# DriverControlsMezzanine.net
KiCad netlist of a schematic drawn in Altium Designer
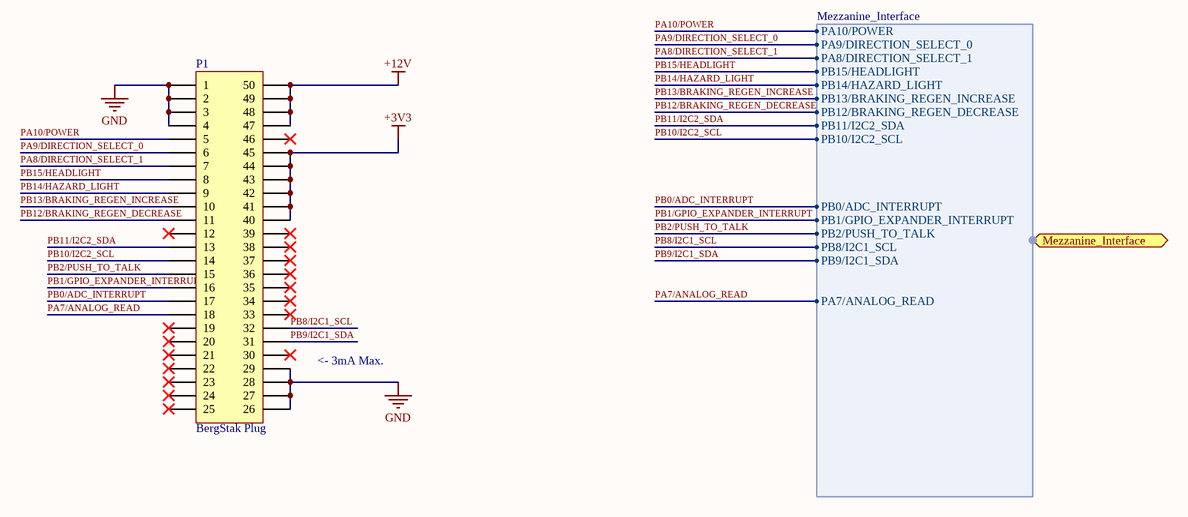
[diagram p0: DriverControlsMezzanine.SchDoc]

(export (version "E")
  (design (tool "Eeschema 10.0.6"))
  (components
    (comp (ref "P1")
      (value "CONN 50POS Bergstak Plug 0.02\"")
      (footprint "CONN, Bergstak 50 Pos Plug")
      (description "50 Position Connector Plug, Outer Shroud Contacts Surface Mount Gold")
      (fields (field (name "SERIES") "BergStak Plug"))
      (libsource (lib "Schematic Diagrams") (part "CONN 50POS Bergstak Plug 0.02{dblquote}"))
    )
  )
  (nets
    (net (code "2") (name "+3V3") (class "Default")
      (node (ref "P1") (pin "40") (pinfunction "40_40") (pintype "passive"))
      (node (ref "P1") (pin "41") (pinfunction "41_41") (pintype "passive"))
      (node (ref "P1") (pin "42") (pinfunction "42_42") (pintype "passive"))
      (node (ref "P1") (pin "43") (pinfunction "43_43") (pintype "passive"))
      (node (ref "P1") (pin "44") (pinfunction "44_44") (pintype "passive"))
      (node (ref "P1") (pin "45") (pinfunction "45_45") (pintype "passive"))
    )
    (net (code "3") (name "+12V") (class "Default")
      (node (ref "P1") (pin "47") (pinfunction "47_47") (pintype "passive"))
      (node (ref "P1") (pin "48") (pinfunction "48_48") (pintype "passive"))
      (node (ref "P1") (pin "49") (pinfunction "49_49") (pintype "passive"))
      (node (ref "P1") (pin "50") (pinfunction "50_50") (pintype "passive"))
    )
    (net (code "4") (name "/PA7{slash}ANALOG_READ") (class "Default")
      (node (ref "P1") (pin "18") (pinfunction "18_18") (pintype "passive"))
    )
    (net (code "5") (name "/PA8{slash}DIRECTION_SELECT_1") (class "Default")
      (node (ref "P1") (pin "7") (pinfunction "7_7") (pintype "passive"))
    )
    (net (code "6") (name "/PA9{slash}DIRECTION_SELECT_0") (class "Default")
      (node (ref "P1") (pin "6") (pinfunction "6_6") (pintype "passive"))
    )
    (net (code "7") (name "/PA10{slash}POWER") (class "Default")
      (node (ref "P1") (pin "5") (pinfunction "5_5") (pintype "passive"))
    )
    (net (code "8") (name "/PB0{slash}ADC_INTERRUPT") (class "Default")
      (node (ref "P1") (pin "17") (pinfunction "17_17") (pintype "passive"))
    )
    (net (code "9") (name "/PB1{slash}GPIO_EXPANDER_INTERRUPT") (class "Default")
      (node (ref "P1") (pin "16") (pinfunction "16_16") (pintype "passive"))
    )
    (net (code "10") (name "/PB2{slash}PUSH_TO_TALK") (class "Default")
      (node (ref "P1") (pin "15") (pinfunction "15_15") (pintype "passive"))
    )
    (net (code "11") (name "/PB8{slash}I2C1_SCL") (class "Default")
      (node (ref "P1") (pin "32") (pinfunction "32_32") (pintype "passive"))
    )
    (net (code "12") (name "/PB9{slash}I2C1_SDA") (class "Default")
      (node (ref "P1") (pin "31") (pinfunction "31_31") (pintype "passive"))
    )
    (net (code "13") (name "/PB10{slash}I2C2_SCL") (class "Default")
      (node (ref "P1") (pin "14") (pinfunction "14_14") (pintype "passive"))
    )
    (net (code "14") (name "/PB11{slash}I2C2_SDA") (class "Default")
      (node (ref "P1") (pin "13") (pinfunction "13_13") (pintype "passive"))
    )
    (net (code "15") (name "/PB12{slash}BRAKING_REGEN_DECREASE") (class "Default")
      (node (ref "P1") (pin "11") (pinfunction "11_11") (pintype "passive"))
    )
    (net (code "16") (name "/PB13{slash}BRAKING_REGEN_INCREASE") (class "Default")
      (node (ref "P1") (pin "10") (pinfunction "10_10") (pintype "passive"))
    )
    (net (code "17") (name "/PB14{slash}HAZARD_LIGHT") (class "Default")
      (node (ref "P1") (pin "9") (pinfunction "9_9") (pintype "passive"))
    )
    (net (code "18") (name "/PB15{slash}HEADLIGHT") (class "Default")
      (node (ref "P1") (pin "8") (pinfunction "8_8") (pintype "passive"))
    )
    (net (code "20") (name "GND") (class "Default")
      (node (ref "P1") (pin "1") (pinfunction "1_1") (pintype "passive"))
      (node (ref "P1") (pin "2") (pinfunction "2_2") (pintype "passive"))
      (node (ref "P1") (pin "26") (pinfunction "26_26") (pintype "passive"))
      (node (ref "P1") (pin "27") (pinfunction "27_27") (pintype "passive"))
      (node (ref "P1") (pin "28") (pinfunction "28_28") (pintype "passive"))
      (node (ref "P1") (pin "29") (pinfunction "29_29") (pintype "passive"))
      (node (ref "P1") (pin "3") (pinfunction "3_3") (pintype "passive"))
      (node (ref "P1") (pin "4") (pinfunction "4_4") (pintype "passive"))
    )
    (net (code "21") (name "unconnected-(P1-Pad12)") (class "Default")
      (node (ref "P1") (pin "12") (pinfunction "12_12") (pintype "passive+no_connect"))
    )
    (net (code "22") (name "unconnected-(P1-Pad19)") (class "Default")
      (node (ref "P1") (pin "19") (pinfunction "19_19") (pintype "passive+no_connect"))
    )
    (net (code "23") (name "unconnected-(P1-Pad20)") (class "Default")
      (node (ref "P1") (pin "20") (pinfunction "20_20") (pintype "passive+no_connect"))
    )
    (net (code "24") (name "unconnected-(P1-Pad21)") (class "Default")
      (node (ref "P1") (pin "21") (pinfunction "21_21") (pintype "passive+no_connect"))
    )
    (net (code "25") (name "unconnected-(P1-Pad22)") (class "Default")
      (node (ref "P1") (pin "22") (pinfunction "22_22") (pintype "passive+no_connect"))
    )
    (net (code "26") (name "unconnected-(P1-Pad23)") (class "Default")
      (node (ref "P1") (pin "23") (pinfunction "23_23") (pintype "passive+no_connect"))
    )
    (net (code "27") (name "unconnected-(P1-Pad24)") (class "Default")
      (node (ref "P1") (pin "24") (pinfunction "24_24") (pintype "passive+no_connect"))
    )
    (net (code "28") (name "unconnected-(P1-Pad25)") (class "Default")
      (node (ref "P1") (pin "25") (pinfunction "25_25") (pintype "passive+no_connect"))
    )
    (net (code "29") (name "unconnected-(P1-Pad30)") (class "Default")
      (node (ref "P1") (pin "30") (pinfunction "30_30") (pintype "passive+no_connect"))
    )
    (net (code "30") (name "unconnected-(P1-Pad33)") (class "Default")
      (node (ref "P1") (pin "33") (pinfunction "33_33") (pintype "passive+no_connect"))
    )
    (net (code "31") (name "unconnected-(P1-Pad34)") (class "Default")
      (node (ref "P1") (pin "34") (pinfunction "34_34") (pintype "passive+no_connect"))
    )
    (net (code "32") (name "unconnected-(P1-Pad35)") (class "Default")
      (node (ref "P1") (pin "35") (pinfunction "35_35") (pintype "passive+no_connect"))
    )
    (net (code "33") (name "unconnected-(P1-Pad36)") (class "Default")
      (node (ref "P1") (pin "36") (pinfunction "36_36") (pintype "passive+no_connect"))
    )
    (net (code "34") (name "unconnected-(P1-Pad37)") (class "Default")
      (node (ref "P1") (pin "37") (pinfunction "37_37") (pintype "passive+no_connect"))
    )
    (net (code "35") (name "unconnected-(P1-Pad38)") (class "Default")
      (node (ref "P1") (pin "38") (pinfunction "38_38") (pintype "passive+no_connect"))
    )
    (net (code "36") (name "unconnected-(P1-Pad39)") (class "Default")
      (node (ref "P1") (pin "39") (pinfunction "39_39") (pintype "passive+no_connect"))
    )
    (net (code "37") (name "unconnected-(P1-Pad46)") (class "Default")
      (node (ref "P1") (pin "46") (pinfunction "46_46") (pintype "passive+no_connect"))
    )
  )
)
